# Keyboard_KEYS.net
KiCad netlist of a schematic drawn in Altium Designer
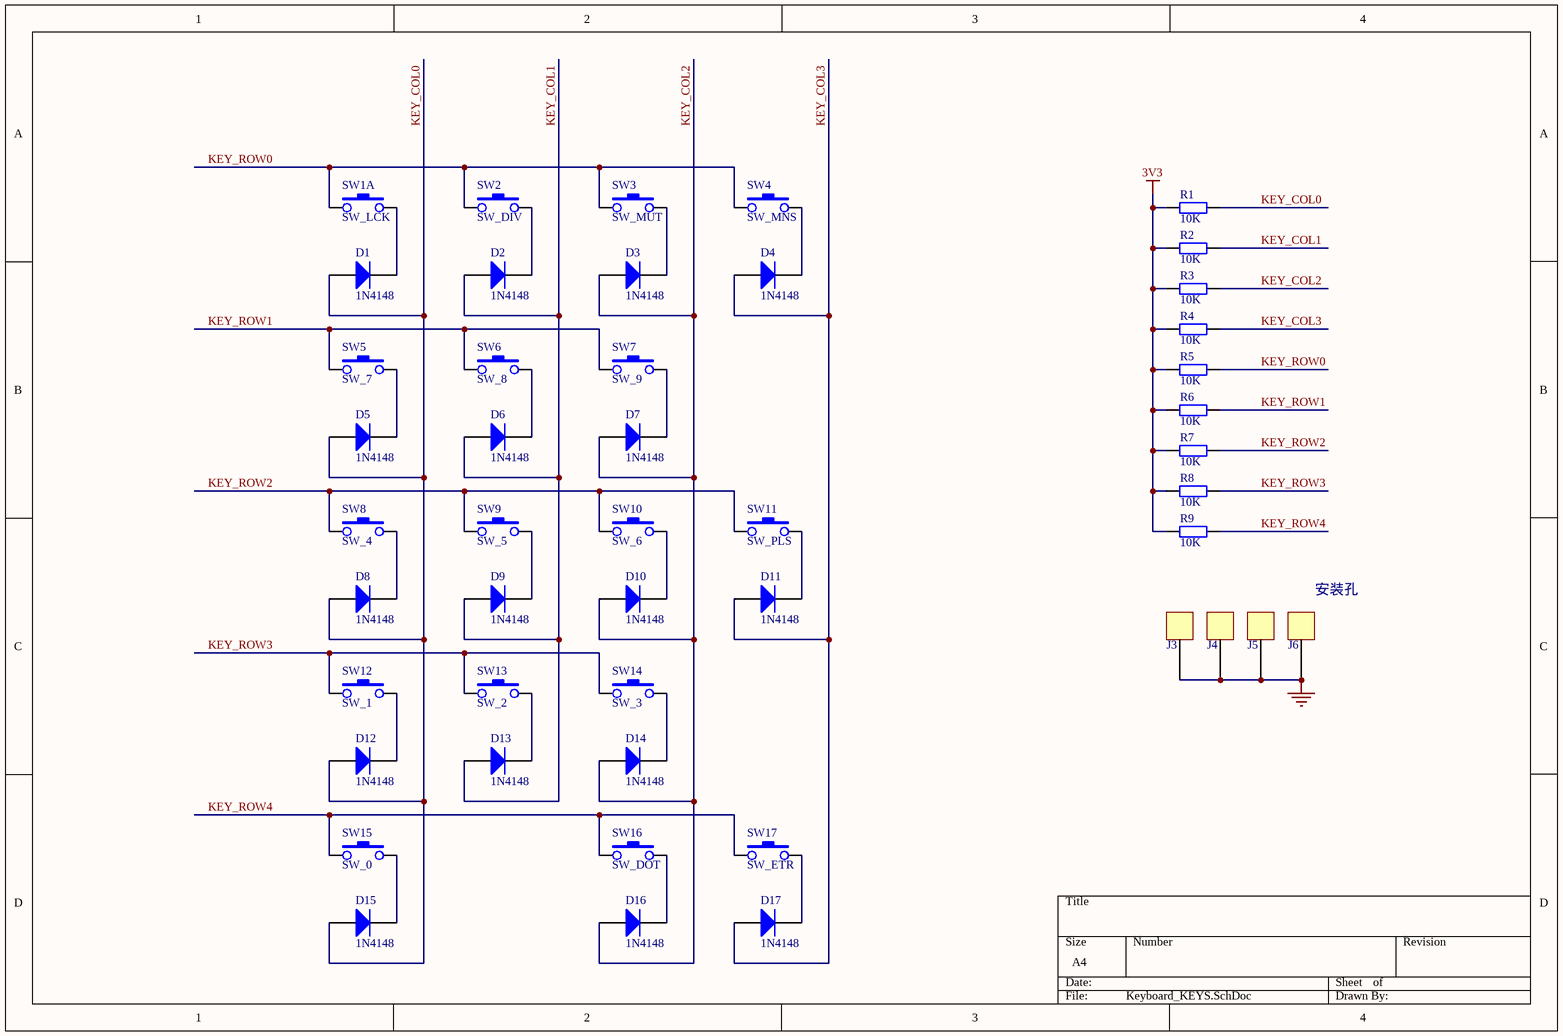
[diagram p0: Keyboard_KEYS.SchDoc]

(export (version "E")
  (design (tool "Eeschema 10.0.6"))
  (components
    (comp (ref "D1")
      (value "1N4148")
      (footprint "Devices:SOD80")
      (description "Default Diode")
      (libsource (lib "Miscellaneous Devices") (part "Diode"))
    )
    (comp (ref "D2")
      (value "1N4148")
      (footprint "Devices:SOD80")
      (description "Default Diode")
      (libsource (lib "Miscellaneous Devices") (part "Diode"))
    )
    (comp (ref "D3")
      (value "1N4148")
      (footprint "Devices:SOD80")
      (description "Default Diode")
      (libsource (lib "Miscellaneous Devices") (part "Diode"))
    )
    (comp (ref "D4")
      (value "1N4148")
      (footprint "Devices:SOD80")
      (description "Default Diode")
      (libsource (lib "Miscellaneous Devices") (part "Diode"))
    )
    (comp (ref "D5")
      (value "1N4148")
      (footprint "Devices:SOD80")
      (description "Default Diode")
      (libsource (lib "Miscellaneous Devices") (part "Diode"))
    )
    (comp (ref "D6")
      (value "1N4148")
      (footprint "Devices:SOD80")
      (description "Default Diode")
      (libsource (lib "Miscellaneous Devices") (part "Diode"))
    )
    (comp (ref "D7")
      (value "1N4148")
      (footprint "Devices:SOD80")
      (description "Default Diode")
      (libsource (lib "Miscellaneous Devices") (part "Diode"))
    )
    (comp (ref "D8")
      (value "1N4148")
      (footprint "Devices:SOD80")
      (description "Default Diode")
      (libsource (lib "Miscellaneous Devices") (part "Diode"))
    )
    (comp (ref "D9")
      (value "1N4148")
      (footprint "Devices:SOD80")
      (description "Default Diode")
      (libsource (lib "Miscellaneous Devices") (part "Diode"))
    )
    (comp (ref "D10")
      (value "1N4148")
      (footprint "Devices:SOD80")
      (description "Default Diode")
      (libsource (lib "Miscellaneous Devices") (part "Diode"))
    )
    (comp (ref "D11")
      (value "1N4148")
      (footprint "Devices:SOD80")
      (description "Default Diode")
      (libsource (lib "Miscellaneous Devices") (part "Diode"))
    )
    (comp (ref "D12")
      (value "1N4148")
      (footprint "Devices:SOD80")
      (description "Default Diode")
      (libsource (lib "Miscellaneous Devices") (part "Diode"))
    )
    (comp (ref "D13")
      (value "1N4148")
      (footprint "Devices:SOD80")
      (description "Default Diode")
      (libsource (lib "Miscellaneous Devices") (part "Diode"))
    )
    (comp (ref "D14")
      (value "1N4148")
      (footprint "Devices:SOD80")
      (description "Default Diode")
      (libsource (lib "Miscellaneous Devices") (part "Diode"))
    )
    (comp (ref "D15")
      (value "1N4148")
      (footprint "Devices:SOD80")
      (description "Default Diode")
      (libsource (lib "Miscellaneous Devices") (part "Diode"))
    )
    (comp (ref "D16")
      (value "1N4148")
      (footprint "Devices:SOD80")
      (description "Default Diode")
      (libsource (lib "Miscellaneous Devices") (part "Diode"))
    )
    (comp (ref "D17")
      (value "1N4148")
      (footprint "Devices:SOD80")
      (description "Default Diode")
      (libsource (lib "Miscellaneous Devices") (part "Diode"))
    )
    (comp (ref "J3") (value "Hole") (footprint "Devices:PADR3/4") (libsource (lib "Devices") (part "Hole")))
    (comp (ref "J4") (value "Hole") (footprint "Devices:PADR3/4") (libsource (lib "Devices") (part "Hole")))
    (comp (ref "J5") (value "Hole") (footprint "Devices:PADR3/4") (libsource (lib "Devices") (part "Hole")))
    (comp (ref "J6") (value "Hole") (footprint "Devices:PADR3/4") (libsource (lib "Devices") (part "Hole")))
    (comp (ref "R1")
      (value "10K")
      (footprint "Devices:R0603")
      (description "Resistor")
      (fields (field (name "PUBLISHER") "Altium Limited"))
      (libsource (lib "Miscellaneous Devices") (part "Res2"))
    )
    (comp (ref "R2")
      (value "10K")
      (footprint "Devices:R0603")
      (description "Resistor")
      (fields (field (name "PUBLISHER") "Altium Limited"))
      (libsource (lib "Miscellaneous Devices") (part "Res2"))
    )
    (comp (ref "R3")
      (value "10K")
      (footprint "Devices:R0603")
      (description "Resistor")
      (fields (field (name "PUBLISHER") "Altium Limited"))
      (libsource (lib "Miscellaneous Devices") (part "Res2"))
    )
    (comp (ref "R4")
      (value "10K")
      (footprint "Devices:R0603")
      (description "Resistor")
      (fields (field (name "PUBLISHER") "Altium Limited"))
      (libsource (lib "Miscellaneous Devices") (part "Res2"))
    )
    (comp (ref "R5")
      (value "10K")
      (footprint "Devices:R0603")
      (description "Resistor")
      (fields (field (name "PUBLISHER") "Altium Limited"))
      (libsource (lib "Miscellaneous Devices") (part "Res2"))
    )
    (comp (ref "R6")
      (value "10K")
      (footprint "Devices:R0603")
      (description "Resistor")
      (fields (field (name "PUBLISHER") "Altium Limited"))
      (libsource (lib "Miscellaneous Devices") (part "Res2"))
    )
    (comp (ref "R7")
      (value "10K")
      (footprint "Devices:R0603")
      (description "Resistor")
      (fields (field (name "PUBLISHER") "Altium Limited"))
      (libsource (lib "Miscellaneous Devices") (part "Res2"))
    )
    (comp (ref "R8")
      (value "10K")
      (footprint "Devices:R0603")
      (description "Resistor")
      (fields (field (name "PUBLISHER") "Altium Limited"))
      (libsource (lib "Miscellaneous Devices") (part "Res2"))
    )
    (comp (ref "R9")
      (value "10K")
      (footprint "Devices:R0603")
      (description "Resistor")
      (fields (field (name "PUBLISHER") "Altium Limited"))
      (libsource (lib "Miscellaneous Devices") (part "Res2"))
    )
    (comp (ref "SW1")
      (value "SW_LCK")
      (footprint "Devices:MX_SW-4-1206LED")
      (libsource (lib "Devices") (part "MX_SW-4-1206LED"))
    )
    (comp (ref "SW2")
      (value "SW_DIV")
      (footprint "Devices:MX_SW-4")
      (libsource (lib "Devices") (part "Push Buttom_2"))
    )
    (comp (ref "SW3")
      (value "SW_MUT")
      (footprint "Devices:MX_SW-4")
      (libsource (lib "Devices") (part "Push Buttom_2"))
    )
    (comp (ref "SW4")
      (value "SW_MNS")
      (footprint "Devices:MX_SW-4")
      (libsource (lib "Devices") (part "Push Buttom_2"))
    )
    (comp (ref "SW5")
      (value "SW_7")
      (footprint "Devices:MX_SW-4")
      (libsource (lib "Devices") (part "Push Buttom_2"))
    )
    (comp (ref "SW6")
      (value "SW_8")
      (footprint "Devices:MX_SW-4")
      (libsource (lib "Devices") (part "Push Buttom_2"))
    )
    (comp (ref "SW7")
      (value "SW_9")
      (footprint "Devices:MX_SW-4")
      (libsource (lib "Devices") (part "Push Buttom_2"))
    )
    (comp (ref "SW8")
      (value "SW_4")
      (footprint "Devices:MX_SW-4")
      (libsource (lib "Devices") (part "Push Buttom_2"))
    )
    (comp (ref "SW9")
      (value "SW_5")
      (footprint "Devices:MX_SW-4")
      (libsource (lib "Devices") (part "Push Buttom_2"))
    )
    (comp (ref "SW10")
      (value "SW_6")
      (footprint "Devices:MX_SW-4")
      (libsource (lib "Devices") (part "Push Buttom_2"))
    )
    (comp (ref "SW11")
      (value "SW_PLS")
      (footprint "Devices:MX_SW-4_1x2_r")
      (libsource (lib "Devices") (part "Push Buttom_2"))
    )
    (comp (ref "SW12")
      (value "SW_1")
      (footprint "Devices:MX_SW-4")
      (libsource (lib "Devices") (part "Push Buttom_2"))
    )
    (comp (ref "SW13")
      (value "SW_2")
      (footprint "Devices:MX_SW-4")
      (libsource (lib "Devices") (part "Push Buttom_2"))
    )
    (comp (ref "SW14")
      (value "SW_3")
      (footprint "Devices:MX_SW-4")
      (libsource (lib "Devices") (part "Push Buttom_2"))
    )
    (comp (ref "SW15")
      (value "SW_0")
      (footprint "Devices:MX_SW-4_1x2")
      (libsource (lib "Devices") (part "Push Buttom_2"))
    )
    (comp (ref "SW16")
      (value "SW_DOT")
      (footprint "Devices:MX_SW-4")
      (libsource (lib "Devices") (part "Push Buttom_2"))
    )
    (comp (ref "SW17")
      (value "SW_ETR")
      (footprint "Devices:MX_SW-4_1x2_r")
      (libsource (lib "Devices") (part "Push Buttom_2"))
    )
  )
  (nets
    (net (code "1") (name "/KEY_COL0") (class "Default")
      (node (ref "D1") (pin "1") (pinfunction "A_1") (pintype "passive"))
      (node (ref "D12") (pin "1") (pinfunction "A_1") (pintype "passive"))
      (node (ref "D15") (pin "1") (pinfunction "A_1") (pintype "passive"))
      (node (ref "D5") (pin "1") (pinfunction "A_1") (pintype "passive"))
      (node (ref "D8") (pin "1") (pinfunction "A_1") (pintype "passive"))
      (node (ref "R1") (pin "2") (pinfunction "2_2") (pintype "passive"))
    )
    (net (code "2") (name "/KEY_COL1") (class "Default")
      (node (ref "D13") (pin "1") (pinfunction "A_1") (pintype "passive"))
      (node (ref "D2") (pin "1") (pinfunction "A_1") (pintype "passive"))
      (node (ref "D6") (pin "1") (pinfunction "A_1") (pintype "passive"))
      (node (ref "D9") (pin "1") (pinfunction "A_1") (pintype "passive"))
      (node (ref "R2") (pin "2") (pinfunction "2_2") (pintype "passive"))
    )
    (net (code "3") (name "/KEY_COL2") (class "Default")
      (node (ref "D10") (pin "1") (pinfunction "A_1") (pintype "passive"))
      (node (ref "D14") (pin "1") (pinfunction "A_1") (pintype "passive"))
      (node (ref "D16") (pin "1") (pinfunction "A_1") (pintype "passive"))
      (node (ref "D3") (pin "1") (pinfunction "A_1") (pintype "passive"))
      (node (ref "D7") (pin "1") (pinfunction "A_1") (pintype "passive"))
      (node (ref "R3") (pin "2") (pinfunction "2_2") (pintype "passive"))
    )
    (net (code "4") (name "/KEY_COL3") (class "Default")
      (node (ref "D11") (pin "1") (pinfunction "A_1") (pintype "passive"))
      (node (ref "D17") (pin "1") (pinfunction "A_1") (pintype "passive"))
      (node (ref "D4") (pin "1") (pinfunction "A_1") (pintype "passive"))
      (node (ref "R4") (pin "2") (pinfunction "2_2") (pintype "passive"))
    )
    (net (code "5") (name "/KEY_ROW0") (class "Default")
      (node (ref "R5") (pin "2") (pinfunction "2_2") (pintype "passive"))
      (node (ref "SW1") (pin "1") (pinfunction "1_1") (pintype "passive"))
      (node (ref "SW2") (pin "1") (pinfunction "1_1") (pintype "passive"))
      (node (ref "SW3") (pin "1") (pinfunction "1_1") (pintype "passive"))
      (node (ref "SW4") (pin "1") (pinfunction "1_1") (pintype "passive"))
    )
    (net (code "6") (name "/KEY_ROW1") (class "Default")
      (node (ref "R6") (pin "2") (pinfunction "2_2") (pintype "passive"))
      (node (ref "SW5") (pin "1") (pinfunction "1_1") (pintype "passive"))
      (node (ref "SW6") (pin "1") (pinfunction "1_1") (pintype "passive"))
      (node (ref "SW7") (pin "1") (pinfunction "1_1") (pintype "passive"))
    )
    (net (code "7") (name "/KEY_ROW2") (class "Default")
      (node (ref "R7") (pin "2") (pinfunction "2_2") (pintype "passive"))
      (node (ref "SW10") (pin "1") (pinfunction "1_1") (pintype "passive"))
      (node (ref "SW11") (pin "1") (pinfunction "1_1") (pintype "passive"))
      (node (ref "SW8") (pin "1") (pinfunction "1_1") (pintype "passive"))
      (node (ref "SW9") (pin "1") (pinfunction "1_1") (pintype "passive"))
    )
    (net (code "8") (name "/KEY_ROW3") (class "Default")
      (node (ref "R8") (pin "2") (pinfunction "2_2") (pintype "passive"))
      (node (ref "SW12") (pin "1") (pinfunction "1_1") (pintype "passive"))
      (node (ref "SW13") (pin "1") (pinfunction "1_1") (pintype "passive"))
      (node (ref "SW14") (pin "1") (pinfunction "1_1") (pintype "passive"))
    )
    (net (code "9") (name "/KEY_ROW4") (class "Default")
      (node (ref "R9") (pin "2") (pinfunction "2_2") (pintype "passive"))
      (node (ref "SW15") (pin "1") (pinfunction "1_1") (pintype "passive"))
      (node (ref "SW16") (pin "1") (pinfunction "1_1") (pintype "passive"))
      (node (ref "SW17") (pin "1") (pinfunction "1_1") (pintype "passive"))
    )
    (net (code "10") (name "3V3") (class "Default")
      (node (ref "R1") (pin "1") (pinfunction "1_1") (pintype "passive"))
      (node (ref "R2") (pin "1") (pinfunction "1_1") (pintype "passive"))
      (node (ref "R3") (pin "1") (pinfunction "1_1") (pintype "passive"))
      (node (ref "R4") (pin "1") (pinfunction "1_1") (pintype "passive"))
      (node (ref "R5") (pin "1") (pinfunction "1_1") (pintype "passive"))
      (node (ref "R6") (pin "1") (pinfunction "1_1") (pintype "passive"))
      (node (ref "R7") (pin "1") (pinfunction "1_1") (pintype "passive"))
      (node (ref "R8") (pin "1") (pinfunction "1_1") (pintype "passive"))
      (node (ref "R9") (pin "1") (pinfunction "1_1") (pintype "passive"))
    )
    (net (code "11") (name "GND") (class "Default")
      (node (ref "J3") (pin "1") (pinfunction "1_1") (pintype "passive"))
      (node (ref "J4") (pin "1") (pinfunction "1_1") (pintype "passive"))
      (node (ref "J5") (pin "1") (pinfunction "1_1") (pintype "passive"))
      (node (ref "J6") (pin "1") (pinfunction "1_1") (pintype "passive"))
    )
    (net (code "12") (name "Net-(D1-K)") (class "Default")
      (node (ref "D1") (pin "2") (pinfunction "K_2") (pintype "passive"))
      (node (ref "SW1") (pin "2") (pinfunction "2_2") (pintype "passive"))
    )
    (net (code "13") (name "Net-(D2-K)") (class "Default")
      (node (ref "D2") (pin "2") (pinfunction "K_2") (pintype "passive"))
      (node (ref "SW2") (pin "2") (pinfunction "2_2") (pintype "passive"))
    )
    (net (code "14") (name "Net-(D3-K)") (class "Default")
      (node (ref "D3") (pin "2") (pinfunction "K_2") (pintype "passive"))
      (node (ref "SW3") (pin "2") (pinfunction "2_2") (pintype "passive"))
    )
    (net (code "15") (name "Net-(D4-K)") (class "Default")
      (node (ref "D4") (pin "2") (pinfunction "K_2") (pintype "passive"))
      (node (ref "SW4") (pin "2") (pinfunction "2_2") (pintype "passive"))
    )
    (net (code "16") (name "Net-(D5-K)") (class "Default")
      (node (ref "D5") (pin "2") (pinfunction "K_2") (pintype "passive"))
      (node (ref "SW5") (pin "2") (pinfunction "2_2") (pintype "passive"))
    )
    (net (code "17") (name "Net-(D6-K)") (class "Default")
      (node (ref "D6") (pin "2") (pinfunction "K_2") (pintype "passive"))
      (node (ref "SW6") (pin "2") (pinfunction "2_2") (pintype "passive"))
    )
    (net (code "18") (name "Net-(D7-K)") (class "Default")
      (node (ref "D7") (pin "2") (pinfunction "K_2") (pintype "passive"))
      (node (ref "SW7") (pin "2") (pinfunction "2_2") (pintype "passive"))
    )
    (net (code "19") (name "Net-(D8-K)") (class "Default")
      (node (ref "D8") (pin "2") (pinfunction "K_2") (pintype "passive"))
      (node (ref "SW8") (pin "2") (pinfunction "2_2") (pintype "passive"))
    )
    (net (code "20") (name "Net-(D9-K)") (class "Default")
      (node (ref "D9") (pin "2") (pinfunction "K_2") (pintype "passive"))
      (node (ref "SW9") (pin "2") (pinfunction "2_2") (pintype "passive"))
    )
    (net (code "21") (name "Net-(D10-K)") (class "Default")
      (node (ref "D10") (pin "2") (pinfunction "K_2") (pintype "passive"))
      (node (ref "SW10") (pin "2") (pinfunction "2_2") (pintype "passive"))
    )
    (net (code "22") (name "Net-(D11-K)") (class "Default")
      (node (ref "D11") (pin "2") (pinfunction "K_2") (pintype "passive"))
      (node (ref "SW11") (pin "2") (pinfunction "2_2") (pintype "passive"))
    )
    (net (code "23") (name "Net-(D12-K)") (class "Default")
      (node (ref "D12") (pin "2") (pinfunction "K_2") (pintype "passive"))
      (node (ref "SW12") (pin "2") (pinfunction "2_2") (pintype "passive"))
    )
    (net (code "24") (name "Net-(D13-K)") (class "Default")
      (node (ref "D13") (pin "2") (pinfunction "K_2") (pintype "passive"))
      (node (ref "SW13") (pin "2") (pinfunction "2_2") (pintype "passive"))
    )
    (net (code "25") (name "Net-(D14-K)") (class "Default")
      (node (ref "D14") (pin "2") (pinfunction "K_2") (pintype "passive"))
      (node (ref "SW14") (pin "2") (pinfunction "2_2") (pintype "passive"))
    )
    (net (code "26") (name "Net-(D15-K)") (class "Default")
      (node (ref "D15") (pin "2") (pinfunction "K_2") (pintype "passive"))
      (node (ref "SW15") (pin "2") (pinfunction "2_2") (pintype "passive"))
    )
    (net (code "27") (name "Net-(D16-K)") (class "Default")
      (node (ref "D16") (pin "2") (pinfunction "K_2") (pintype "passive"))
      (node (ref "SW16") (pin "2") (pinfunction "2_2") (pintype "passive"))
    )
    (net (code "28") (name "Net-(D17-K)") (class "Default")
      (node (ref "D17") (pin "2") (pinfunction "K_2") (pintype "passive"))
      (node (ref "SW17") (pin "2") (pinfunction "2_2") (pintype "passive"))
    )
  )
)
